# Sunday.net
KiCad netlist of a schematic drawn in Altium Designer
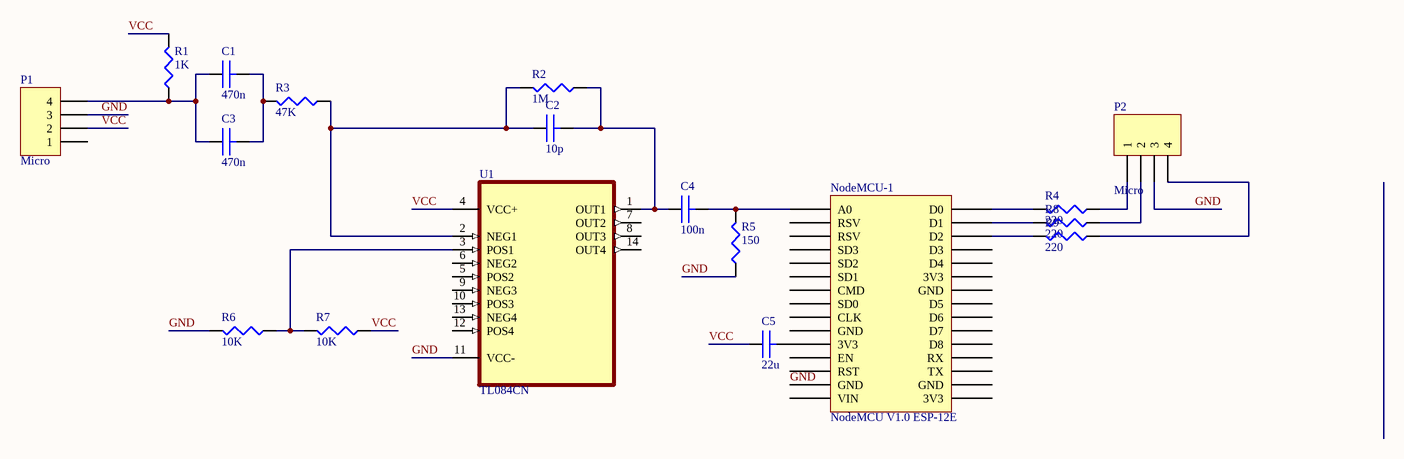
[diagram p0: Sunday.SchDoc]

(export (version "E")
  (design (tool "Eeschema 10.0.6"))
  (components
    (comp (ref "C1")
      (value "470n")
      (footprint "RAD0.2")
      (description "capacité non polarisée")
      (fields (field (name "Comment") "CAP"))
      (libsource (lib "ISEN_basics") (part "CAP"))
    )
    (comp (ref "C2")
      (value "10p")
      (footprint "RAD0.2")
      (description "capacité non polarisée")
      (fields (field (name "Comment") "CAP"))
      (libsource (lib "ISEN_basics") (part "CAP"))
    )
    (comp (ref "C3")
      (value "470n")
      (footprint "RAD0.2")
      (description "capacité non polarisée")
      (fields (field (name "Comment") "CAP"))
      (libsource (lib "ISEN_basics") (part "CAP"))
    )
    (comp (ref "C4")
      (value "100n")
      (footprint "RAD0.2")
      (description "capacité non polarisée")
      (fields (field (name "Comment") "CAP"))
      (libsource (lib "ISEN_basics") (part "CAP"))
    )
    (comp (ref "C5")
      (value "22u")
      (footprint "RAD0.2")
      (description "capacité non polarisée")
      (fields (field (name "Comment") "CAP"))
      (libsource (lib "ISEN_basics") (part "CAP"))
    )
    (comp (ref "NodeMCU-1")
      (value "NodeMCU V1.0 ESP-12E")
      (footprint "NodeMCU V1.0 ESP-12E")
      (description "NodeMCU V1.0 ESP8266 (ESP-12E)")
      (libsource (lib "nodemcu") (part "NodeMCU V1.0 ESP-12E"))
    )
    (comp (ref "P1")
      (value "Micro")
      (footprint "HDR1X4")
      (description "Header, 4-Pin")
      (fields (field (name "PUBLISHER") "Altium Limited"))
      (libsource (lib "Miscellaneous Connectors") (part "Header 4"))
    )
    (comp (ref "P2")
      (value "Micro")
      (footprint "HDR1X4")
      (description "Header, 4-Pin")
      (fields (field (name "PUBLISHER") "Altium Limited"))
      (libsource (lib "") (part "Header 4_1"))
    )
    (comp (ref "R1")
      (value "1K")
      (footprint "AXIAL0.4")
      (description "resistance")
      (fields (field (name "Comment") "RES"))
      (libsource (lib "ISEN_basics") (part "RES"))
    )
    (comp (ref "R2")
      (value "1M")
      (footprint "AXIAL0.4")
      (description "resistance")
      (fields (field (name "Comment") "RES"))
      (libsource (lib "ISEN_basics") (part "RES"))
    )
    (comp (ref "R3")
      (value "47K")
      (footprint "AXIAL0.4")
      (description "resistance")
      (fields (field (name "Comment") "RES"))
      (libsource (lib "ISEN_basics") (part "RES"))
    )
    (comp (ref "R4")
      (value "220")
      (footprint "AXIAL0.4")
      (description "resistance")
      (fields (field (name "Comment") "RES"))
      (libsource (lib "ISEN_basics") (part "RES"))
    )
    (comp (ref "R5")
      (value "150")
      (footprint "AXIAL0.4")
      (description "resistance")
      (fields (field (name "Comment") "RES"))
      (libsource (lib "ISEN_basics") (part "RES"))
    )
    (comp (ref "R6")
      (value "10K")
      (footprint "AXIAL0.4")
      (description "resistance")
      (fields (field (name "Comment") "RES"))
      (libsource (lib "ISEN_basics") (part "RES"))
    )
    (comp (ref "R7")
      (value "10K")
      (footprint "AXIAL0.4")
      (description "resistance")
      (fields (field (name "Comment") "RES"))
      (libsource (lib "ISEN_basics") (part "RES"))
    )
    (comp (ref "R8")
      (value "220")
      (footprint "AXIAL0.4")
      (description "resistance")
      (fields (field (name "Comment") "RES"))
      (libsource (lib "ISEN_basics") (part "RES"))
    )
    (comp (ref "R9")
      (value "220")
      (footprint "AXIAL0.4")
      (description "resistance")
      (fields (field (name "Comment") "RES"))
      (libsource (lib "ISEN_basics") (part "RES"))
    )
    (comp (ref "U1")
      (value "TL084CN")
      (footprint "DIP254P762X510-14")
      (description "J-FET Amplifier 4 Circuit 14-DIP")
      (fields (field (name "MF") "STMicroelectronics"))
      (libsource (lib "TL084CN") (part "TL084CN"))
    )
  )
  (nets
    (net (code "1") (name "/GND") (class "Default")
      (node (ref "NodeMCU-1") (pin "GND") (pinfunction "GND_GND") (pintype "passive"))
      (node (ref "P1") (pin "3") (pinfunction "3_3") (pintype "passive"))
      (node (ref "P2") (pin "3") (pinfunction "3_3") (pintype "passive"))
      (node (ref "R5") (pin "1") (pintype "passive"))
      (node (ref "R6") (pin "2") (pintype "passive"))
      (node (ref "U1") (pin "11") (pinfunction "VCC-_11") (pintype "power_in"))
    )
    (net (code "2") (name "/VCC") (class "Default")
      (node (ref "C5") (pin "1") (pinfunction "1_1") (pintype "passive"))
      (node (ref "P1") (pin "2") (pinfunction "2_2") (pintype "passive"))
      (node (ref "R1") (pin "2") (pintype "passive"))
      (node (ref "R7") (pin "1") (pintype "passive"))
      (node (ref "U1") (pin "4") (pinfunction "VCC+_4") (pintype "power_in"))
    )
    (net (code "3") (name "Net-(C1-Pad1)") (class "Default")
      (node (ref "C1") (pin "1") (pinfunction "1_1") (pintype "passive"))
      (node (ref "C3") (pin "1") (pinfunction "1_1") (pintype "passive"))
      (node (ref "P1") (pin "4") (pinfunction "4_4") (pintype "passive"))
      (node (ref "R1") (pin "1") (pintype "passive"))
    )
    (net (code "4") (name "Net-(C1-Pad2)") (class "Default")
      (node (ref "C1") (pin "2") (pinfunction "2_2") (pintype "passive"))
      (node (ref "C3") (pin "2") (pinfunction "2_2") (pintype "passive"))
      (node (ref "R3") (pin "2") (pintype "passive"))
    )
    (net (code "5") (name "Net-(C4-Pad2)") (class "Default")
      (node (ref "C4") (pin "2") (pinfunction "2_2") (pintype "passive"))
      (node (ref "NodeMCU-1") (pin "A0") (pinfunction "A0_A0") (pintype "passive"))
      (node (ref "R5") (pin "2") (pintype "passive"))
    )
    (net (code "6") (name "Net-(C5-Pad2)") (class "Default")
      (node (ref "C5") (pin "2") (pinfunction "2_2") (pintype "passive"))
      (node (ref "NodeMCU-1") (pin "3V3") (pinfunction "3V3_3V3") (pintype "passive"))
    )
    (net (code "7") (name "Net-(NodeMCU-1-PadD0)") (class "Default")
      (node (ref "NodeMCU-1") (pin "D0") (pinfunction "D0_D0") (pintype "passive"))
      (node (ref "R4") (pin "2") (pintype "passive"))
    )
    (net (code "8") (name "Net-(NodeMCU-1-PadD1)") (class "Default")
      (node (ref "NodeMCU-1") (pin "D1") (pinfunction "D1_D1") (pintype "passive"))
      (node (ref "R8") (pin "2") (pintype "passive"))
    )
    (net (code "9") (name "Net-(NodeMCU-1-PadD2)") (class "Default")
      (node (ref "NodeMCU-1") (pin "D2") (pinfunction "D2_D2") (pintype "passive"))
      (node (ref "R9") (pin "2") (pintype "passive"))
    )
    (net (code "10") (name "Net-(P2-Pad1)") (class "Default")
      (node (ref "P2") (pin "1") (pinfunction "1_1") (pintype "passive"))
      (node (ref "R4") (pin "1") (pintype "passive"))
    )
    (net (code "11") (name "Net-(P2-Pad2)") (class "Default")
      (node (ref "P2") (pin "2") (pinfunction "2_2") (pintype "passive"))
      (node (ref "R8") (pin "1") (pintype "passive"))
    )
    (net (code "12") (name "Net-(P2-Pad4)") (class "Default")
      (node (ref "P2") (pin "4") (pinfunction "4_4") (pintype "passive"))
      (node (ref "R9") (pin "1") (pintype "passive"))
    )
    (net (code "13") (name "Net-(U1-NEG1)") (class "Default")
      (node (ref "C2") (pin "1") (pinfunction "1_1") (pintype "passive"))
      (node (ref "R2") (pin "2") (pintype "passive"))
      (node (ref "R3") (pin "1") (pintype "passive"))
      (node (ref "U1") (pin "2") (pinfunction "NEG1_2") (pintype "input"))
    )
    (net (code "14") (name "Net-(U1-OUT1)") (class "Default")
      (node (ref "C2") (pin "2") (pinfunction "2_2") (pintype "passive"))
      (node (ref "C4") (pin "1") (pinfunction "1_1") (pintype "passive"))
      (node (ref "R2") (pin "1") (pintype "passive"))
      (node (ref "U1") (pin "1") (pinfunction "OUT1_1") (pintype "output"))
    )
    (net (code "15") (name "Net-(U1-POS1)") (class "Default")
      (node (ref "R6") (pin "1") (pintype "passive"))
      (node (ref "R7") (pin "2") (pintype "passive"))
      (node (ref "U1") (pin "3") (pinfunction "POS1_3") (pintype "input"))
    )
    (net (code "16") (name "unconnected-(NodeMCU-1-Pad3V3)") (class "Default")
      (node (ref "NodeMCU-1") (pin "3V3") (pinfunction "3V3_3V3") (pintype "passive"))
    )
    (net (code "17") (name "unconnected-(NodeMCU-1-Pad3V3)_1") (class "Default")
      (node (ref "NodeMCU-1") (pin "3V3") (pinfunction "3V3_3V3") (pintype "passive"))
    )
    (net (code "18") (name "unconnected-(NodeMCU-1-PadCLK)") (class "Default")
      (node (ref "NodeMCU-1") (pin "CLK") (pinfunction "CLK_CLK") (pintype "passive"))
    )
    (net (code "19") (name "unconnected-(NodeMCU-1-PadCMD)") (class "Default")
      (node (ref "NodeMCU-1") (pin "CMD") (pinfunction "CMD_CMD") (pintype "passive"))
    )
    (net (code "20") (name "unconnected-(NodeMCU-1-PadD3)") (class "Default")
      (node (ref "NodeMCU-1") (pin "D3") (pinfunction "D3_D3") (pintype "passive"))
    )
    (net (code "21") (name "unconnected-(NodeMCU-1-PadD4)") (class "Default")
      (node (ref "NodeMCU-1") (pin "D4") (pinfunction "D4_D4") (pintype "passive"))
    )
    (net (code "22") (name "unconnected-(NodeMCU-1-PadD5)") (class "Default")
      (node (ref "NodeMCU-1") (pin "D5") (pinfunction "D5_D5") (pintype "passive"))
    )
    (net (code "23") (name "unconnected-(NodeMCU-1-PadD6)") (class "Default")
      (node (ref "NodeMCU-1") (pin "D6") (pinfunction "D6_D6") (pintype "passive"))
    )
    (net (code "24") (name "unconnected-(NodeMCU-1-PadD7)") (class "Default")
      (node (ref "NodeMCU-1") (pin "D7") (pinfunction "D7_D7") (pintype "passive"))
    )
    (net (code "25") (name "unconnected-(NodeMCU-1-PadD8)") (class "Default")
      (node (ref "NodeMCU-1") (pin "D8") (pinfunction "D8_D8") (pintype "passive"))
    )
    (net (code "26") (name "unconnected-(NodeMCU-1-PadEN)") (class "Default")
      (node (ref "NodeMCU-1") (pin "EN") (pinfunction "EN_EN") (pintype "passive"))
    )
    (net (code "27") (name "unconnected-(NodeMCU-1-PadGND)") (class "Default")
      (node (ref "NodeMCU-1") (pin "GND") (pinfunction "GND_GND") (pintype "passive"))
    )
    (net (code "28") (name "unconnected-(NodeMCU-1-PadGND)_1") (class "Default")
      (node (ref "NodeMCU-1") (pin "GND") (pinfunction "GND_GND") (pintype "passive"))
    )
    (net (code "29") (name "unconnected-(NodeMCU-1-PadGND)_2") (class "Default")
      (node (ref "NodeMCU-1") (pin "GND") (pinfunction "GND_GND") (pintype "passive"))
    )
    (net (code "30") (name "unconnected-(NodeMCU-1-PadRST)") (class "Default")
      (node (ref "NodeMCU-1") (pin "RST") (pinfunction "RST_RST") (pintype "passive"))
    )
    (net (code "31") (name "unconnected-(NodeMCU-1-PadRSV)") (class "Default")
      (node (ref "NodeMCU-1") (pin "RSV") (pinfunction "RSV_RSV") (pintype "passive"))
    )
    (net (code "32") (name "unconnected-(NodeMCU-1-PadRSV)_1") (class "Default")
      (node (ref "NodeMCU-1") (pin "RSV") (pinfunction "RSV_RSV") (pintype "passive"))
    )
    (net (code "33") (name "unconnected-(NodeMCU-1-PadRX)") (class "Default")
      (node (ref "NodeMCU-1") (pin "RX") (pinfunction "RX_RX") (pintype "passive"))
    )
    (net (code "34") (name "unconnected-(NodeMCU-1-PadSD0)") (class "Default")
      (node (ref "NodeMCU-1") (pin "SD0") (pinfunction "SD0_SD0") (pintype "passive"))
    )
    (net (code "35") (name "unconnected-(NodeMCU-1-PadSD1)") (class "Default")
      (node (ref "NodeMCU-1") (pin "SD1") (pinfunction "SD1_SD1") (pintype "passive"))
    )
    (net (code "36") (name "unconnected-(NodeMCU-1-PadSD2)") (class "Default")
      (node (ref "NodeMCU-1") (pin "SD2") (pinfunction "SD2_SD2") (pintype "passive"))
    )
    (net (code "37") (name "unconnected-(NodeMCU-1-PadSD3)") (class "Default")
      (node (ref "NodeMCU-1") (pin "SD3") (pinfunction "SD3_SD3") (pintype "passive"))
    )
    (net (code "38") (name "unconnected-(NodeMCU-1-PadTX)") (class "Default")
      (node (ref "NodeMCU-1") (pin "TX") (pinfunction "TX_TX") (pintype "passive"))
    )
    (net (code "39") (name "unconnected-(NodeMCU-1-PadVIN)") (class "Default")
      (node (ref "NodeMCU-1") (pin "VIN") (pinfunction "VIN_VIN") (pintype "passive"))
    )
    (net (code "40") (name "unconnected-(P1-Pad1)") (class "Default")
      (node (ref "P1") (pin "1") (pinfunction "1_1") (pintype "passive"))
    )
    (net (code "41") (name "unconnected-(U1-NEG2-Pad6)") (class "Default")
      (node (ref "U1") (pin "6") (pinfunction "NEG2_6") (pintype "input"))
    )
    (net (code "42") (name "unconnected-(U1-NEG3-Pad9)") (class "Default")
      (node (ref "U1") (pin "9") (pinfunction "NEG3_9") (pintype "input"))
    )
    (net (code "43") (name "unconnected-(U1-NEG4-Pad13)") (class "Default")
      (node (ref "U1") (pin "13") (pinfunction "NEG4_13") (pintype "input"))
    )
    (net (code "44") (name "unconnected-(U1-OUT2-Pad7)") (class "Default")
      (node (ref "U1") (pin "7") (pinfunction "OUT2_7") (pintype "output"))
    )
    (net (code "45") (name "unconnected-(U1-OUT3-Pad8)") (class "Default")
      (node (ref "U1") (pin "8") (pinfunction "OUT3_8") (pintype "output"))
    )
    (net (code "46") (name "unconnected-(U1-OUT4-Pad14)") (class "Default")
      (node (ref "U1") (pin "14") (pinfunction "OUT4_14") (pintype "output"))
    )
    (net (code "47") (name "unconnected-(U1-POS2-Pad5)") (class "Default")
      (node (ref "U1") (pin "5") (pinfunction "POS2_5") (pintype "input"))
    )
    (net (code "48") (name "unconnected-(U1-POS3-Pad10)") (class "Default")
      (node (ref "U1") (pin "10") (pinfunction "POS3_10") (pintype "input"))
    )
    (net (code "49") (name "unconnected-(U1-POS4-Pad12)") (class "Default")
      (node (ref "U1") (pin "12") (pinfunction "POS4_12") (pintype "input"))
    )
  )
)
